# Power.net
KiCad netlist of a schematic drawn in Altium Designer
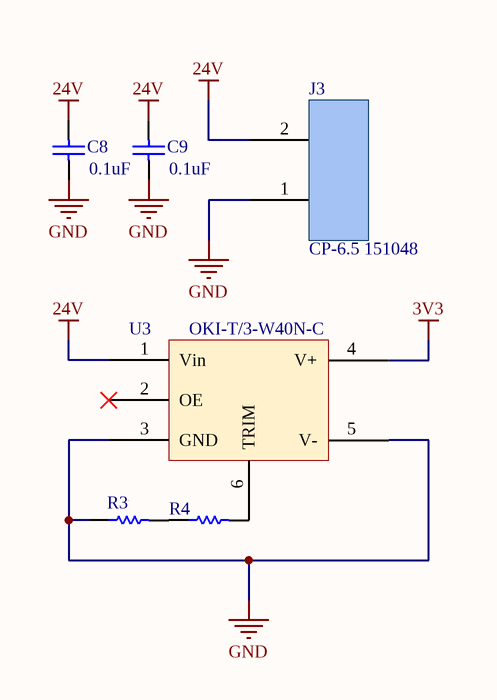
[diagram p0: Power.SchDoc]

(export (version "E")
  (design (tool "Eeschema 10.0.6"))
  (components
    (comp (ref "C8")
      (value "0.1uF")
      (footprint "CAPC3216X100X50LL20T25")
      (description "CAP CER 0.1UF 25V 10% X7R 1206")
      (fields (field (name "PARTNUMBER") "C1206F104K3RACTU"))
      (libsource (lib "Altium Content Vault") (part "CAP-NP-2"))
    )
    (comp (ref "C9")
      (value "0.1uF")
      (footprint "CAPC3216X100X50LL20T25")
      (description "CAP CER 0.1UF 25V 10% X7R 1206")
      (fields (field (name "PARTNUMBER") "C1206F104K3RACTU"))
      (libsource (lib "Altium Content Vault") (part "CAP-NP-2"))
    )
    (comp (ref "J3")
      (value "CP-6.5 151048")
      (description "Connector Header Through Hole 2 position")
      (libsource (lib "HRTAltiumLib") (part "CP-6.5 151048"))
    )
    (comp (ref "R3")
      (value "RES SMD 6.2K OHM 5% 1/4W 1206")
      (footprint "RESC1206(3216)_L")
      (fields (field (name "TOLERANCE") "0.5%") (field (name "POWER") "0.25 W"))
      (libsource (lib "Altium Content Vault") (part "RES"))
    )
    (comp (ref "R4")
      (value "RES SMD 6.2K OHM 5% 1/4W 1206")
      (footprint "RESC1206(3216)_L")
      (description "RES SMD 1.54K OHM 0.1% 1/4W 1206")
      (fields (field (name "TOLERANCE") "0.5%") (field (name "POWER") "0.25 W"))
      (libsource (lib "Altium Content Vault") (part "RES"))
    )
    (comp (ref "U3") (value "OKI-T/3-W40N-C") (libsource (lib "HRTAltiumLib") (part "OKI-T/3-W40N-C")))
  )
  (nets
    (net (code "1") (name "3V3") (class "Default")
      (node (ref "U3") (pin "4") (pinfunction "V+_4") (pintype "passive"))
    )
    (net (code "2") (name "24V") (class "Default")
      (node (ref "C8") (pin "1") (pinfunction "1_1") (pintype "passive"))
      (node (ref "C9") (pin "1") (pinfunction "1_1") (pintype "passive"))
      (node (ref "J3") (pin "2") (pinfunction "2_2") (pintype "passive"))
      (node (ref "U3") (pin "1") (pinfunction "Vin_1") (pintype "passive"))
    )
    (net (code "3") (name "GND") (class "Default")
      (node (ref "C8") (pin "2") (pinfunction "2_2") (pintype "passive"))
      (node (ref "C9") (pin "2") (pinfunction "2_2") (pintype "passive"))
      (node (ref "J3") (pin "1") (pinfunction "1_1") (pintype "passive"))
      (node (ref "R3") (pin "1") (pinfunction "1_1") (pintype "passive"))
      (node (ref "U3") (pin "3") (pinfunction "GND_3") (pintype "passive"))
      (node (ref "U3") (pin "5") (pinfunction "V-_5") (pintype "passive"))
    )
    (net (code "4") (name "Net-(R3-Pad2)") (class "Default")
      (node (ref "R3") (pin "2") (pinfunction "2_2") (pintype "passive"))
      (node (ref "R4") (pin "1") (pinfunction "1_1") (pintype "passive"))
    )
    (net (code "5") (name "Net-(U3-TRIM)") (class "Default")
      (node (ref "R4") (pin "2") (pinfunction "2_2") (pintype "passive"))
      (node (ref "U3") (pin "6") (pinfunction "TRIM_6") (pintype "passive"))
    )
    (net (code "6") (name "unconnected-(U3-OE-Pad2)") (class "Default")
      (node (ref "U3") (pin "2") (pinfunction "OE_2") (pintype "passive+no_connect"))
    )
  )
)
